# RdL_main_v03_simple.net
KiCad netlist of a schematic drawn in EAGLE
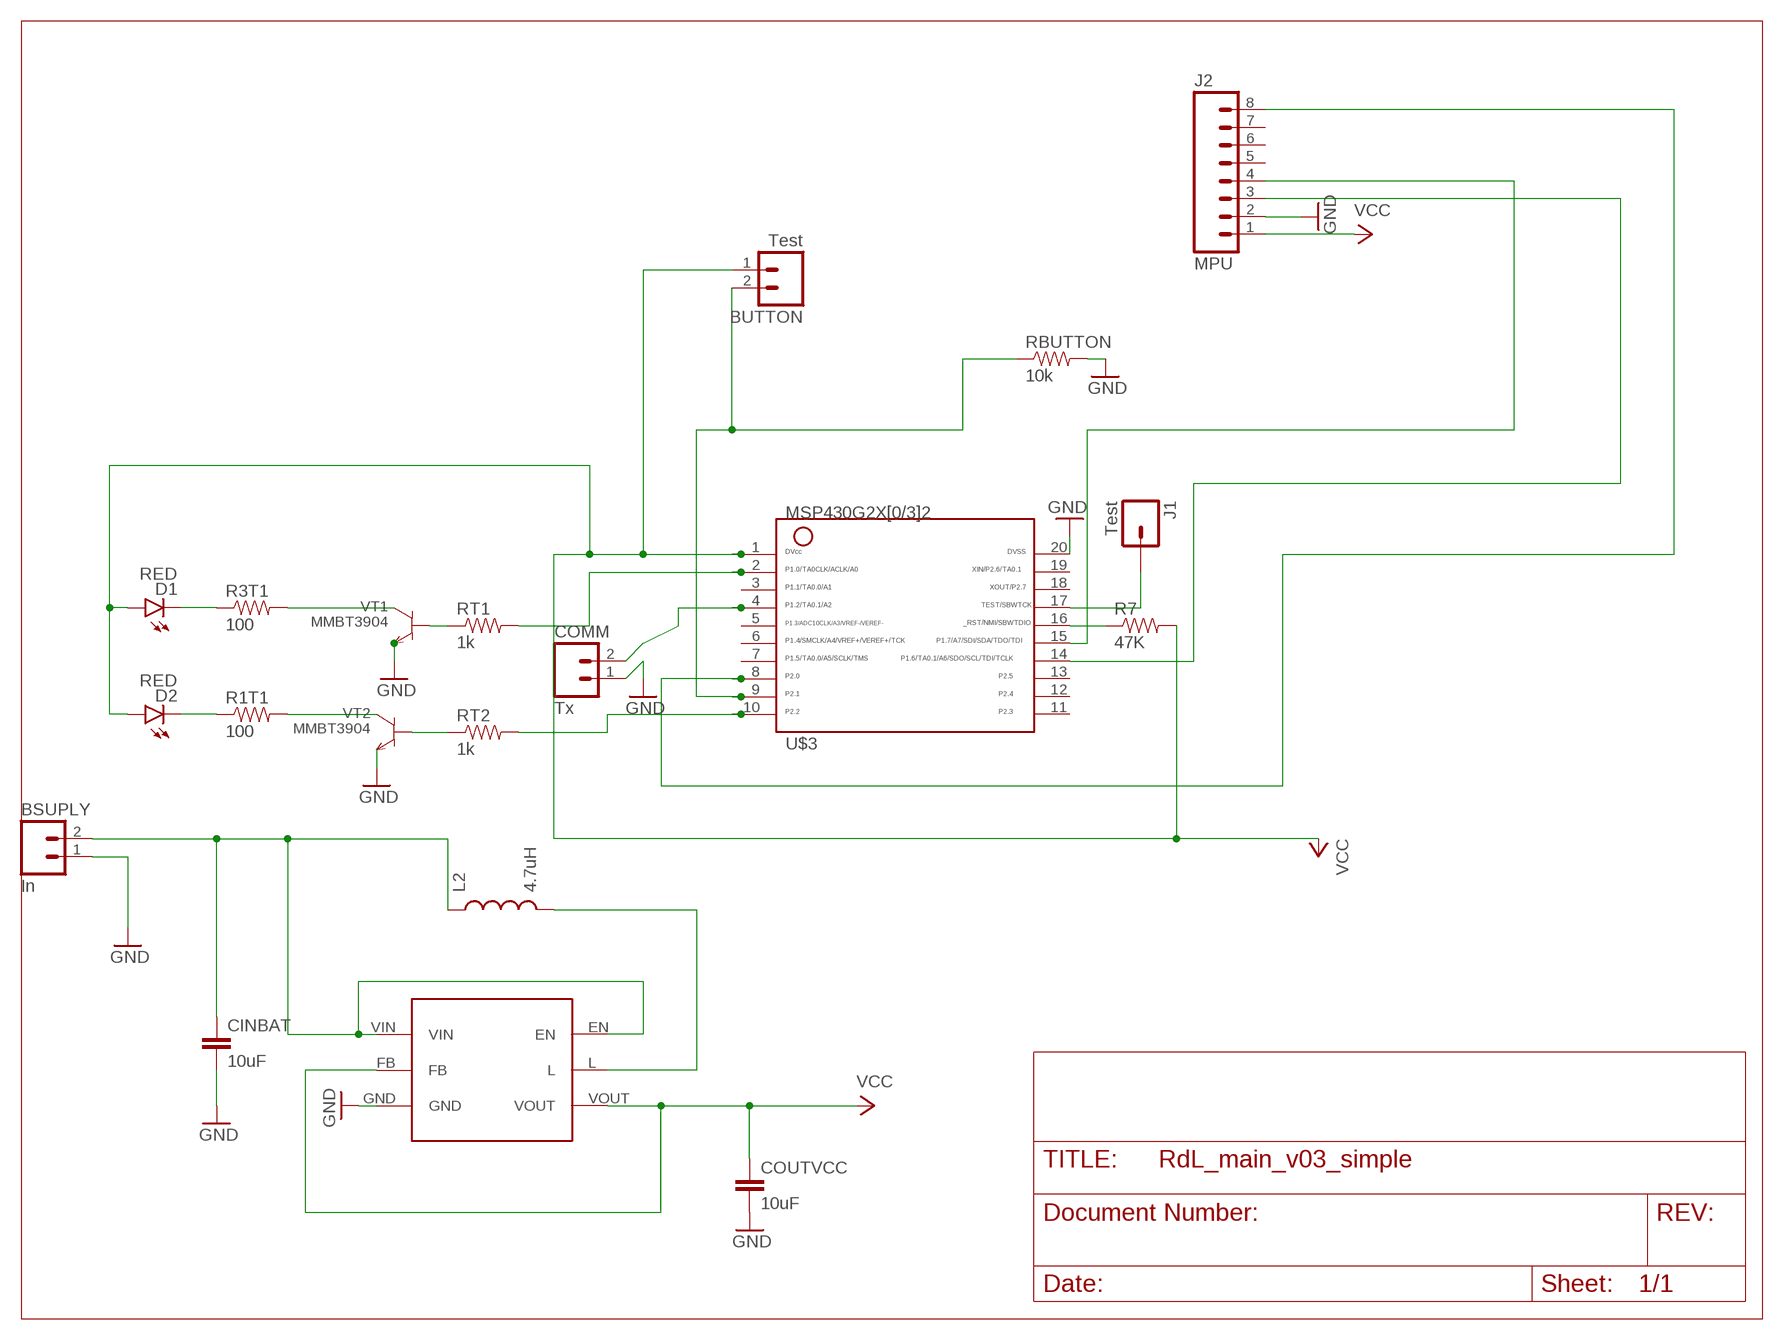
[diagram p0: schematic, sheet 1]

(export (version "E")
  (design (tool "Eeschema 10.0.6"))
  (components
    (comp (ref "BSUPLY")
      (value "In")
      (footprint "eagle-import:1X02")
      (libsource (lib "eagle-import") (part "M02PTH"))
    )
    (comp (ref "BUTTON")
      (value "Test")
      (footprint "eagle-import:1X02")
      (libsource (lib "eagle-import") (part "M02PTH"))
    )
    (comp (ref "CINBAT")
      (value "10uF")
      (footprint "eagle-import:0805")
      (libsource (lib "eagle-import") (part "CAP0805"))
    )
    (comp (ref "COMM")
      (value "Tx")
      (footprint "eagle-import:1X02")
      (libsource (lib "eagle-import") (part "M02PTH"))
    )
    (comp (ref "COUTVCC")
      (value "10uF")
      (footprint "eagle-import:0805")
      (libsource (lib "eagle-import") (part "CAP0805"))
    )
    (comp (ref "D1")
      (value "RED")
      (footprint "eagle-import:LED-1206")
      (libsource (lib "eagle-import") (part "LED-RED1206"))
    )
    (comp (ref "D2")
      (value "RED")
      (footprint "eagle-import:LED-1206")
      (libsource (lib "eagle-import") (part "LED-RED1206"))
    )
    (comp (ref "J1")
      (value "Test")
      (footprint "eagle-import:1X01")
      (libsource (lib "eagle-import") (part "M01PTH"))
    )
    (comp (ref "J2")
      (value "MPU")
      (footprint "eagle-import:1X08_PIN1_NO_SILK")
      (libsource (lib "eagle-import") (part "M08NO_SILK"))
    )
    (comp (ref "L2")
      (value "4.7uH")
      (footprint "eagle-import:INDUCTOR_4.7UH")
      (libsource (lib "eagle-import") (part "INDUCTORINDUCTOR_4.7UH"))
    )
    (comp (ref "R1T1")
      (value "100")
      (footprint "eagle-import:1206")
      (libsource (lib "eagle-import") (part "RESISTOR1206"))
    )
    (comp (ref "R3T1")
      (value "100")
      (footprint "eagle-import:1206")
      (libsource (lib "eagle-import") (part "RESISTOR1206"))
    )
    (comp (ref "R7")
      (value "47K")
      (footprint "eagle-import:0603-RES")
      (libsource (lib "eagle-import") (part "47KOHM1/10W1%(0603)"))
    )
    (comp (ref "RBUTTON")
      (value "10k")
      (footprint "eagle-import:0805")
      (libsource (lib "eagle-import") (part "RESISTOR0805-RES"))
    )
    (comp (ref "RT1")
      (value "1k")
      (footprint "eagle-import:1206")
      (libsource (lib "eagle-import") (part "RESISTOR1206"))
    )
    (comp (ref "RT2")
      (value "1k")
      (footprint "eagle-import:1206")
      (libsource (lib "eagle-import") (part "RESISTOR1206"))
    )
    (comp (ref "U$1")
      (value "TLV61225")
      (footprint "eagle-import:TLV61225DCKT")
      (libsource (lib "eagle-import") (part "TLV61225"))
    )
    (comp (ref "U$3")
      (value "G2X[0/3]2---PW20")
      (footprint "eagle-import:PW20")
      (libsource (lib "eagle-import") (part "G2X[0/3]2---PW20"))
    )
    (comp (ref "VT1")
      (value "MMBT3904")
      (footprint "eagle-import:SOT23-BEC")
      (libsource (lib "eagle-import") (part "MMBT3904"))
    )
    (comp (ref "VT2")
      (value "MMBT3904")
      (footprint "eagle-import:SOT23-BEC")
      (libsource (lib "eagle-import") (part "MMBT3904"))
    )
  )
  (nets
    (net (code "1") (name "GND") (class "Default")
      (node (ref "BSUPLY") (pin "1") (pinfunction "1_1") (pintype "passive"))
      (node (ref "CINBAT") (pin "2") (pinfunction "2_2") (pintype "passive"))
      (node (ref "COMM") (pin "1") (pinfunction "1_1") (pintype "passive"))
      (node (ref "COUTVCC") (pin "2") (pinfunction "2_2") (pintype "passive"))
      (node (ref "J2") (pin "2") (pinfunction "2_2") (pintype "passive"))
      (node (ref "RBUTTON") (pin "2") (pinfunction "2_2") (pintype "passive"))
      (node (ref "U$1") (pin "GND") (pinfunction "GND_GND") (pintype "bidirectional"))
      (node (ref "U$3") (pin "20") (pinfunction "20_20") (pintype "bidirectional"))
      (node (ref "VT1") (pin "E") (pinfunction "E_E") (pintype "passive"))
      (node (ref "VT2") (pin "E") (pinfunction "E_E") (pintype "passive"))
    )
    (net (code "2") (name "Net-(BUTTON-Pad2)") (class "Default")
      (node (ref "BUTTON") (pin "2") (pinfunction "2_2") (pintype "passive"))
      (node (ref "RBUTTON") (pin "1") (pinfunction "1_1") (pintype "passive"))
      (node (ref "U$3") (pin "9") (pinfunction "9_9") (pintype "bidirectional"))
    )
    (net (code "3") (name "Net-(COMM-Pad2)") (class "Default")
      (node (ref "COMM") (pin "2") (pinfunction "2_2") (pintype "passive"))
      (node (ref "U$3") (pin "4") (pinfunction "4_4") (pintype "bidirectional"))
    )
    (net (code "4") (name "Net-(D1-PadC)") (class "Default")
      (node (ref "D1") (pin "C") (pinfunction "C_C") (pintype "passive"))
      (node (ref "R3T1") (pin "1") (pinfunction "1_1") (pintype "passive"))
    )
    (net (code "5") (name "Net-(D2-PadC)") (class "Default")
      (node (ref "D2") (pin "C") (pinfunction "C_C") (pintype "passive"))
      (node (ref "R1T1") (pin "1") (pinfunction "1_1") (pintype "passive"))
    )
    (net (code "6") (name "Net-(J1-Pad1)") (class "Default")
      (node (ref "J1") (pin "1") (pinfunction "1_1") (pintype "passive"))
      (node (ref "U$3") (pin "17") (pinfunction "17_17") (pintype "bidirectional"))
    )
    (net (code "7") (name "Net-(J2-Pad3)") (class "Default")
      (node (ref "J2") (pin "3") (pinfunction "3_3") (pintype "passive"))
      (node (ref "U$3") (pin "14") (pinfunction "14_14") (pintype "bidirectional"))
    )
    (net (code "8") (name "Net-(J2-Pad4)") (class "Default")
      (node (ref "J2") (pin "4") (pinfunction "4_4") (pintype "passive"))
      (node (ref "U$3") (pin "15") (pinfunction "15_15") (pintype "bidirectional"))
    )
    (net (code "9") (name "Net-(J2-Pad8)") (class "Default")
      (node (ref "J2") (pin "8") (pinfunction "8_8") (pintype "passive"))
      (node (ref "U$3") (pin "8") (pinfunction "8_8") (pintype "bidirectional"))
    )
    (net (code "10") (name "Net-(L2-1)") (class "Default")
      (node (ref "BSUPLY") (pin "2") (pinfunction "2_2") (pintype "passive"))
      (node (ref "CINBAT") (pin "1") (pinfunction "1_1") (pintype "passive"))
      (node (ref "L2") (pin "P$1") (pinfunction "1_P$1") (pintype "passive"))
      (node (ref "U$1") (pin "EN") (pinfunction "EN_EN") (pintype "bidirectional"))
      (node (ref "U$1") (pin "VIN") (pinfunction "VIN_VIN") (pintype "bidirectional"))
    )
    (net (code "11") (name "Net-(L2-2)") (class "Default")
      (node (ref "L2") (pin "P$2") (pinfunction "2_P$2") (pintype "passive"))
      (node (ref "U$1") (pin "L") (pinfunction "L_L") (pintype "bidirectional"))
    )
    (net (code "12") (name "Net-(R1T1-Pad2)") (class "Default")
      (node (ref "R1T1") (pin "2") (pinfunction "2_2") (pintype "passive"))
      (node (ref "VT2") (pin "C") (pinfunction "C_C") (pintype "passive"))
    )
    (net (code "13") (name "Net-(R3T1-Pad2)") (class "Default")
      (node (ref "R3T1") (pin "2") (pinfunction "2_2") (pintype "passive"))
      (node (ref "VT1") (pin "C") (pinfunction "C_C") (pintype "passive"))
    )
    (net (code "14") (name "Net-(R7-Pad1)") (class "Default")
      (node (ref "R7") (pin "1") (pinfunction "1_1") (pintype "passive"))
      (node (ref "U$3") (pin "16") (pinfunction "16_16") (pintype "bidirectional"))
    )
    (net (code "15") (name "Net-(RT1-Pad1)") (class "Default")
      (node (ref "RT1") (pin "1") (pinfunction "1_1") (pintype "passive"))
      (node (ref "VT1") (pin "B") (pinfunction "B_B") (pintype "passive"))
    )
    (net (code "16") (name "Net-(RT1-Pad2)") (class "Default")
      (node (ref "RT1") (pin "2") (pinfunction "2_2") (pintype "passive"))
      (node (ref "U$3") (pin "2") (pinfunction "2_2") (pintype "bidirectional"))
    )
    (net (code "17") (name "Net-(RT2-Pad1)") (class "Default")
      (node (ref "RT2") (pin "1") (pinfunction "1_1") (pintype "passive"))
      (node (ref "VT2") (pin "B") (pinfunction "B_B") (pintype "passive"))
    )
    (net (code "18") (name "Net-(RT2-Pad2)") (class "Default")
      (node (ref "RT2") (pin "2") (pinfunction "2_2") (pintype "passive"))
      (node (ref "U$3") (pin "10") (pinfunction "10_10") (pintype "bidirectional"))
    )
    (net (code "19") (name "VCC") (class "Default")
      (node (ref "BUTTON") (pin "1") (pinfunction "1_1") (pintype "passive"))
      (node (ref "COUTVCC") (pin "1") (pinfunction "1_1") (pintype "passive"))
      (node (ref "D1") (pin "A") (pinfunction "A_A") (pintype "passive"))
      (node (ref "D2") (pin "A") (pinfunction "A_A") (pintype "passive"))
      (node (ref "J2") (pin "1") (pinfunction "1_1") (pintype "passive"))
      (node (ref "R7") (pin "2") (pinfunction "2_2") (pintype "passive"))
      (node (ref "U$1") (pin "FB") (pinfunction "FB_FB") (pintype "bidirectional"))
      (node (ref "U$1") (pin "VOUT") (pinfunction "VOUT_VOUT") (pintype "bidirectional"))
      (node (ref "U$3") (pin "1") (pinfunction "1_1") (pintype "bidirectional"))
    )
    (net (code "20") (name "unconnected-(J2-Pad5)") (class "Default")
      (node (ref "J2") (pin "5") (pinfunction "5_5") (pintype "passive"))
    )
    (net (code "21") (name "unconnected-(J2-Pad6)") (class "Default")
      (node (ref "J2") (pin "6") (pinfunction "6_6") (pintype "passive"))
    )
    (net (code "22") (name "unconnected-(J2-Pad7)") (class "Default")
      (node (ref "J2") (pin "7") (pinfunction "7_7") (pintype "passive"))
    )
    (net (code "23") (name "unconnected-(U$3-Pad3)") (class "Default")
      (node (ref "U$3") (pin "3") (pinfunction "3_3") (pintype "bidirectional"))
    )
    (net (code "24") (name "unconnected-(U$3-Pad5)") (class "Default")
      (node (ref "U$3") (pin "5") (pinfunction "5_5") (pintype "bidirectional"))
    )
    (net (code "25") (name "unconnected-(U$3-Pad6)") (class "Default")
      (node (ref "U$3") (pin "6") (pinfunction "6_6") (pintype "bidirectional"))
    )
    (net (code "26") (name "unconnected-(U$3-Pad7)") (class "Default")
      (node (ref "U$3") (pin "7") (pinfunction "7_7") (pintype "bidirectional"))
    )
    (net (code "27") (name "unconnected-(U$3-Pad11)") (class "Default")
      (node (ref "U$3") (pin "11") (pinfunction "11_11") (pintype "bidirectional"))
    )
    (net (code "28") (name "unconnected-(U$3-Pad12)") (class "Default")
      (node (ref "U$3") (pin "12") (pinfunction "12_12") (pintype "bidirectional"))
    )
    (net (code "29") (name "unconnected-(U$3-Pad13)") (class "Default")
      (node (ref "U$3") (pin "13") (pinfunction "13_13") (pintype "bidirectional"))
    )
    (net (code "30") (name "unconnected-(U$3-Pad18)") (class "Default")
      (node (ref "U$3") (pin "18") (pinfunction "18_18") (pintype "bidirectional"))
    )
    (net (code "31") (name "unconnected-(U$3-Pad19)") (class "Default")
      (node (ref "U$3") (pin "19") (pinfunction "19_19") (pintype "bidirectional"))
    )
  )
)
